# MyModelTransformed.net
KiCad netlist of a schematic drawn in EAGLE
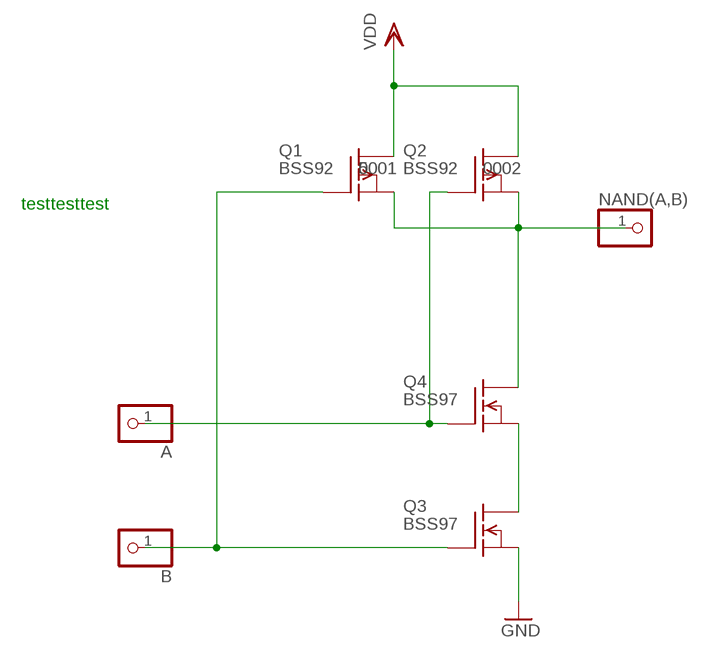
[diagram p0: schematic, sheet 1]

(export (version "E")
  (design (tool "Eeschema 10.0.6"))
  (components
    (comp (ref "A")
      (value "PINHD-1X1")
      (footprint "eagle-import:1X01")
      (fields (field (name "UID") "-1"))
      (libsource (lib "eagle-import") (part "PINHD-1X1"))
    )
    (comp (ref "B")
      (value "PINHD-1X1")
      (footprint "eagle-import:1X01")
      (fields (field (name "UID") "-1"))
      (libsource (lib "eagle-import") (part "PINHD-1X1"))
    )
    (comp (ref "NAND(A,B)")
      (value "PINHD-1X1")
      (footprint "eagle-import:1X01")
      (fields (field (name "UID") "-1"))
      (libsource (lib "eagle-import") (part "PINHD-1X1"))
    )
    (comp (ref "Q1")
      (value "BSS92")
      (footprint "eagle-import:TO92")
      (fields (field (name "P1") "0001") (field (name "TEST2") "5") (field (name "UID") "8"))
      (libsource (lib "eagle-import") (part "BSS92"))
    )
    (comp (ref "Q2")
      (value "BSS92")
      (footprint "eagle-import:TO92")
      (fields (field (name "P2") "0002") (field (name "UID") "-1"))
      (libsource (lib "eagle-import") (part "BSS92"))
    )
    (comp (ref "Q3")
      (value "BSS97")
      (footprint "eagle-import:TO202")
      (fields (field (name "UID") "-1"))
      (libsource (lib "eagle-import") (part "BSS97"))
    )
    (comp (ref "Q4")
      (value "BSS97")
      (footprint "eagle-import:TO202")
      (fields (field (name "UID") "-1"))
      (libsource (lib "eagle-import") (part "BSS97"))
    )
  )
  (nets
    (net (code "1") (name "GND") (class "Default")
      (node (ref "Q3") (pin "1") (pinfunction "S_1") (pintype "passive"))
    )
    (net (code "2") (name "Net-(Q1-G)") (class "Default")
      (node (ref "B") (pin "1") (pinfunction "1_1") (pintype "passive"))
      (node (ref "Q1") (pin "1") (pinfunction "G_1") (pintype "passive"))
      (node (ref "Q3") (pin "3") (pinfunction "G_3") (pintype "passive"))
    )
    (net (code "3") (name "Net-(Q1-S)") (class "Default")
      (node (ref "NAND(A,B)") (pin "1") (pinfunction "1_1") (pintype "passive"))
      (node (ref "Q1") (pin "3") (pinfunction "S_3") (pintype "passive"))
      (node (ref "Q2") (pin "3") (pinfunction "S_3") (pintype "passive"))
      (node (ref "Q4") (pin "2") (pinfunction "D_2") (pintype "passive"))
    )
    (net (code "4") (name "Net-(Q2-G)") (class "Default")
      (node (ref "A") (pin "1") (pinfunction "1_1") (pintype "passive"))
      (node (ref "Q2") (pin "1") (pinfunction "G_1") (pintype "passive"))
      (node (ref "Q4") (pin "3") (pinfunction "G_3") (pintype "passive"))
    )
    (net (code "5") (name "Net-(Q3-D)") (class "Default")
      (node (ref "Q3") (pin "2") (pinfunction "D_2") (pintype "passive"))
      (node (ref "Q4") (pin "1") (pinfunction "S_1") (pintype "passive"))
    )
    (net (code "6") (name "VDD") (class "Default")
      (node (ref "Q1") (pin "2") (pinfunction "D_2") (pintype "passive"))
      (node (ref "Q2") (pin "2") (pinfunction "D_2") (pintype "passive"))
    )
  )
)
